# Task1_Eagle.net
KiCad netlist of a schematic drawn in EAGLE
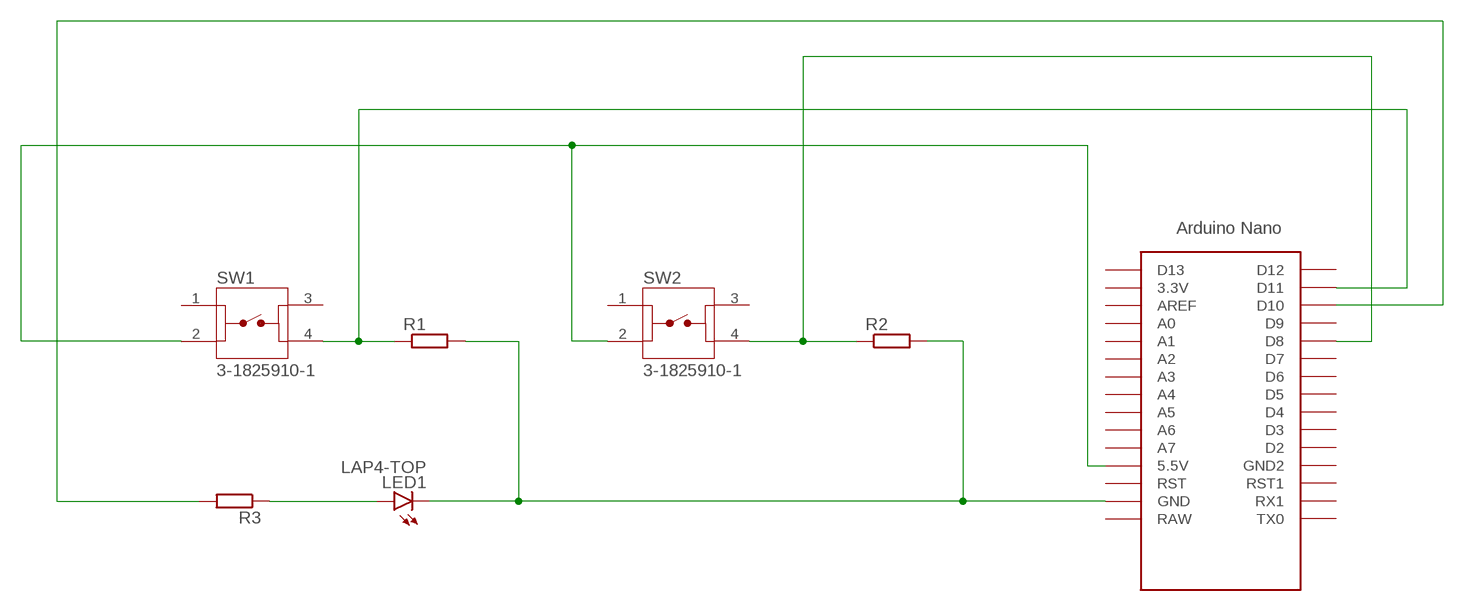
[diagram p0: schematic, sheet 1]

(export (version "E")
  (design (tool "Eeschema 10.0.6"))
  (components
    (comp (ref "LED1")
      (value "LAP4-TOP")
      (footprint "eagle-import:P47F-TOP")
      (libsource (lib "eagle-import") (part "P4-TOPLA"))
    )
    (comp (ref "R1")
      (value "R-EU_0207/12")
      (footprint "eagle-import:0207_12")
      (libsource (lib "eagle-import") (part "R-EU_0207/12"))
    )
    (comp (ref "R2")
      (value "R-EU_0207/12")
      (footprint "eagle-import:0207_12")
      (libsource (lib "eagle-import") (part "R-EU_0207/12"))
    )
    (comp (ref "R3")
      (value "R-EU_0207/12")
      (footprint "eagle-import:0207_12")
      (libsource (lib "eagle-import") (part "R-EU_0207/12"))
    )
    (comp (ref "SW1")
      (value "3-1825910-1")
      (footprint "eagle-import:TE_3-1825910-1")
      (fields (field (name "MF") "TE Connectivity"))
      (libsource (lib "eagle-import") (part "3-1825910-1"))
    )
    (comp (ref "SW2")
      (value "3-1825910-1")
      (footprint "eagle-import:TE_3-1825910-1")
      (fields (field (name "MF") "TE Connectivity"))
      (libsource (lib "eagle-import") (part "3-1825910-1"))
    )
    (comp (ref "U$1")
      (value "NANO")
      (footprint "eagle-import:NANO")
      (libsource (lib "eagle-import") (part "NANO"))
    )
  )
  (nets
    (net (code "1") (name "Net-(LED1-PadA)") (class "Default")
      (node (ref "LED1") (pin "A") (pinfunction "A_A") (pintype "passive"))
      (node (ref "R3") (pin "1") (pinfunction "1_1") (pintype "passive"))
    )
    (net (code "2") (name "Net-(LED1-PadC)") (class "Default")
      (node (ref "LED1") (pin "C") (pinfunction "C_C") (pintype "passive"))
      (node (ref "R1") (pin "2") (pinfunction "2_2") (pintype "passive"))
      (node (ref "R2") (pin "2") (pinfunction "2_2") (pintype "passive"))
      (node (ref "U$1") (pin "GND") (pinfunction "GND_GND") (pintype "bidirectional"))
    )
    (net (code "3") (name "Net-(R1-Pad1)") (class "Default")
      (node (ref "R1") (pin "1") (pinfunction "1_1") (pintype "passive"))
      (node (ref "SW1") (pin "4") (pinfunction "4_4") (pintype "passive"))
      (node (ref "U$1") (pin "D11") (pinfunction "D11_D11") (pintype "bidirectional"))
    )
    (net (code "4") (name "Net-(R2-Pad1)") (class "Default")
      (node (ref "R2") (pin "1") (pinfunction "1_1") (pintype "passive"))
      (node (ref "SW2") (pin "4") (pinfunction "4_4") (pintype "passive"))
      (node (ref "U$1") (pin "D8") (pinfunction "D8_D8") (pintype "bidirectional"))
    )
    (net (code "5") (name "Net-(R3-Pad2)") (class "Default")
      (node (ref "R3") (pin "2") (pinfunction "2_2") (pintype "passive"))
      (node (ref "U$1") (pin "D10") (pinfunction "D10_D10") (pintype "bidirectional"))
    )
    (net (code "6") (name "Net-(U$1-5.5V)") (class "Default")
      (node (ref "SW1") (pin "2") (pinfunction "2_2") (pintype "passive"))
      (node (ref "SW2") (pin "2") (pinfunction "2_2") (pintype "passive"))
      (node (ref "U$1") (pin "5V") (pinfunction "5.5V_5V") (pintype "bidirectional"))
    )
    (net (code "7") (name "unconnected-(SW1-Pad1)") (class "Default")
      (node (ref "SW1") (pin "1") (pinfunction "1_1") (pintype "passive"))
    )
    (net (code "8") (name "unconnected-(SW1-Pad3)") (class "Default")
      (node (ref "SW1") (pin "3") (pinfunction "3_3") (pintype "passive"))
    )
    (net (code "9") (name "unconnected-(SW2-Pad1)") (class "Default")
      (node (ref "SW2") (pin "1") (pinfunction "1_1") (pintype "passive"))
    )
    (net (code "10") (name "unconnected-(SW2-Pad3)") (class "Default")
      (node (ref "SW2") (pin "3") (pinfunction "3_3") (pintype "passive"))
    )
    (net (code "11") (name "unconnected-(U$1-GND2-PadGND1)") (class "Default")
      (node (ref "U$1") (pin "GND1") (pinfunction "GND2_GND1") (pintype "bidirectional"))
    )
    (net (code "12") (name "unconnected-(U$1-Pad3.3V)") (class "Default")
      (node (ref "U$1") (pin "3.3V") (pinfunction "3.3V_3.3V") (pintype "bidirectional"))
    )
    (net (code "13") (name "unconnected-(U$1-PadA0)") (class "Default")
      (node (ref "U$1") (pin "A0") (pinfunction "A0_A0") (pintype "bidirectional"))
    )
    (net (code "14") (name "unconnected-(U$1-PadA1)") (class "Default")
      (node (ref "U$1") (pin "A1") (pinfunction "A1_A1") (pintype "bidirectional"))
    )
    (net (code "15") (name "unconnected-(U$1-PadA2)") (class "Default")
      (node (ref "U$1") (pin "A2") (pinfunction "A2_A2") (pintype "bidirectional"))
    )
    (net (code "16") (name "unconnected-(U$1-PadA3)") (class "Default")
      (node (ref "U$1") (pin "A3") (pinfunction "A3_A3") (pintype "bidirectional"))
    )
    (net (code "17") (name "unconnected-(U$1-PadA4)") (class "Default")
      (node (ref "U$1") (pin "A4") (pinfunction "A4_A4") (pintype "bidirectional"))
    )
    (net (code "18") (name "unconnected-(U$1-PadA5)") (class "Default")
      (node (ref "U$1") (pin "A5") (pinfunction "A5_A5") (pintype "bidirectional"))
    )
    (net (code "19") (name "unconnected-(U$1-PadA6)") (class "Default")
      (node (ref "U$1") (pin "A6") (pinfunction "A6_A6") (pintype "bidirectional"))
    )
    (net (code "20") (name "unconnected-(U$1-PadA7)") (class "Default")
      (node (ref "U$1") (pin "A7") (pinfunction "A7_A7") (pintype "bidirectional"))
    )
    (net (code "21") (name "unconnected-(U$1-PadAREF)") (class "Default")
      (node (ref "U$1") (pin "AREF") (pinfunction "AREF_AREF") (pintype "bidirectional"))
    )
    (net (code "22") (name "unconnected-(U$1-PadD2)") (class "Default")
      (node (ref "U$1") (pin "D2") (pinfunction "D2_D2") (pintype "bidirectional"))
    )
    (net (code "23") (name "unconnected-(U$1-PadD3)") (class "Default")
      (node (ref "U$1") (pin "D3") (pinfunction "D3_D3") (pintype "bidirectional"))
    )
    (net (code "24") (name "unconnected-(U$1-PadD4)") (class "Default")
      (node (ref "U$1") (pin "D4") (pinfunction "D4_D4") (pintype "bidirectional"))
    )
    (net (code "25") (name "unconnected-(U$1-PadD5)") (class "Default")
      (node (ref "U$1") (pin "D5") (pinfunction "D5_D5") (pintype "bidirectional"))
    )
    (net (code "26") (name "unconnected-(U$1-PadD6)") (class "Default")
      (node (ref "U$1") (pin "D6") (pinfunction "D6_D6") (pintype "bidirectional"))
    )
    (net (code "27") (name "unconnected-(U$1-PadD7)") (class "Default")
      (node (ref "U$1") (pin "D7") (pinfunction "D7_D7") (pintype "bidirectional"))
    )
    (net (code "28") (name "unconnected-(U$1-PadD9)") (class "Default")
      (node (ref "U$1") (pin "D9") (pinfunction "D9_D9") (pintype "bidirectional"))
    )
    (net (code "29") (name "unconnected-(U$1-PadD12)") (class "Default")
      (node (ref "U$1") (pin "D12") (pinfunction "D12_D12") (pintype "bidirectional"))
    )
    (net (code "30") (name "unconnected-(U$1-PadD13)") (class "Default")
      (node (ref "U$1") (pin "D13") (pinfunction "D13_D13") (pintype "bidirectional"))
    )
    (net (code "31") (name "unconnected-(U$1-PadICSP1)") (class "Default")
      (node (ref "U$1") (pin "ICSP1") (pinfunction "ICSP1_ICSP1") (pintype "bidirectional"))
    )
    (net (code "32") (name "unconnected-(U$1-PadICSP2)") (class "Default")
      (node (ref "U$1") (pin "ICSP2") (pinfunction "ICSP2_ICSP2") (pintype "bidirectional"))
    )
    (net (code "33") (name "unconnected-(U$1-PadICSP3)") (class "Default")
      (node (ref "U$1") (pin "ICSP3") (pinfunction "ICSP3_ICSP3") (pintype "bidirectional"))
    )
    (net (code "34") (name "unconnected-(U$1-PadICSP4)") (class "Default")
      (node (ref "U$1") (pin "ICSP4") (pinfunction "ICSP4_ICSP4") (pintype "bidirectional"))
    )
    (net (code "35") (name "unconnected-(U$1-PadICSP5)") (class "Default")
      (node (ref "U$1") (pin "ICSP5") (pinfunction "ICSP5_ICSP5") (pintype "bidirectional"))
    )
    (net (code "36") (name "unconnected-(U$1-PadICSP6)") (class "Default")
      (node (ref "U$1") (pin "ICSP6") (pinfunction "ICSP6_ICSP6") (pintype "bidirectional"))
    )
    (net (code "37") (name "unconnected-(U$1-PadRAW)") (class "Default")
      (node (ref "U$1") (pin "RAW") (pinfunction "RAW_RAW") (pintype "bidirectional"))
    )
    (net (code "38") (name "unconnected-(U$1-PadRST)") (class "Default")
      (node (ref "U$1") (pin "RST") (pinfunction "RST_RST") (pintype "bidirectional"))
    )
    (net (code "39") (name "unconnected-(U$1-PadRST1)") (class "Default")
      (node (ref "U$1") (pin "RST1") (pinfunction "RST1_RST1") (pintype "bidirectional"))
    )
    (net (code "40") (name "unconnected-(U$1-PadRX1)") (class "Default")
      (node (ref "U$1") (pin "RX1") (pinfunction "RX1_RX1") (pintype "bidirectional"))
    )
    (net (code "41") (name "unconnected-(U$1-PadTX0)") (class "Default")
      (node (ref "U$1") (pin "TX0") (pinfunction "TX0_TX0") (pintype "bidirectional"))
    )
  )
)
